# Schematic.net
KiCad netlist of a schematic drawn in Altium Designer
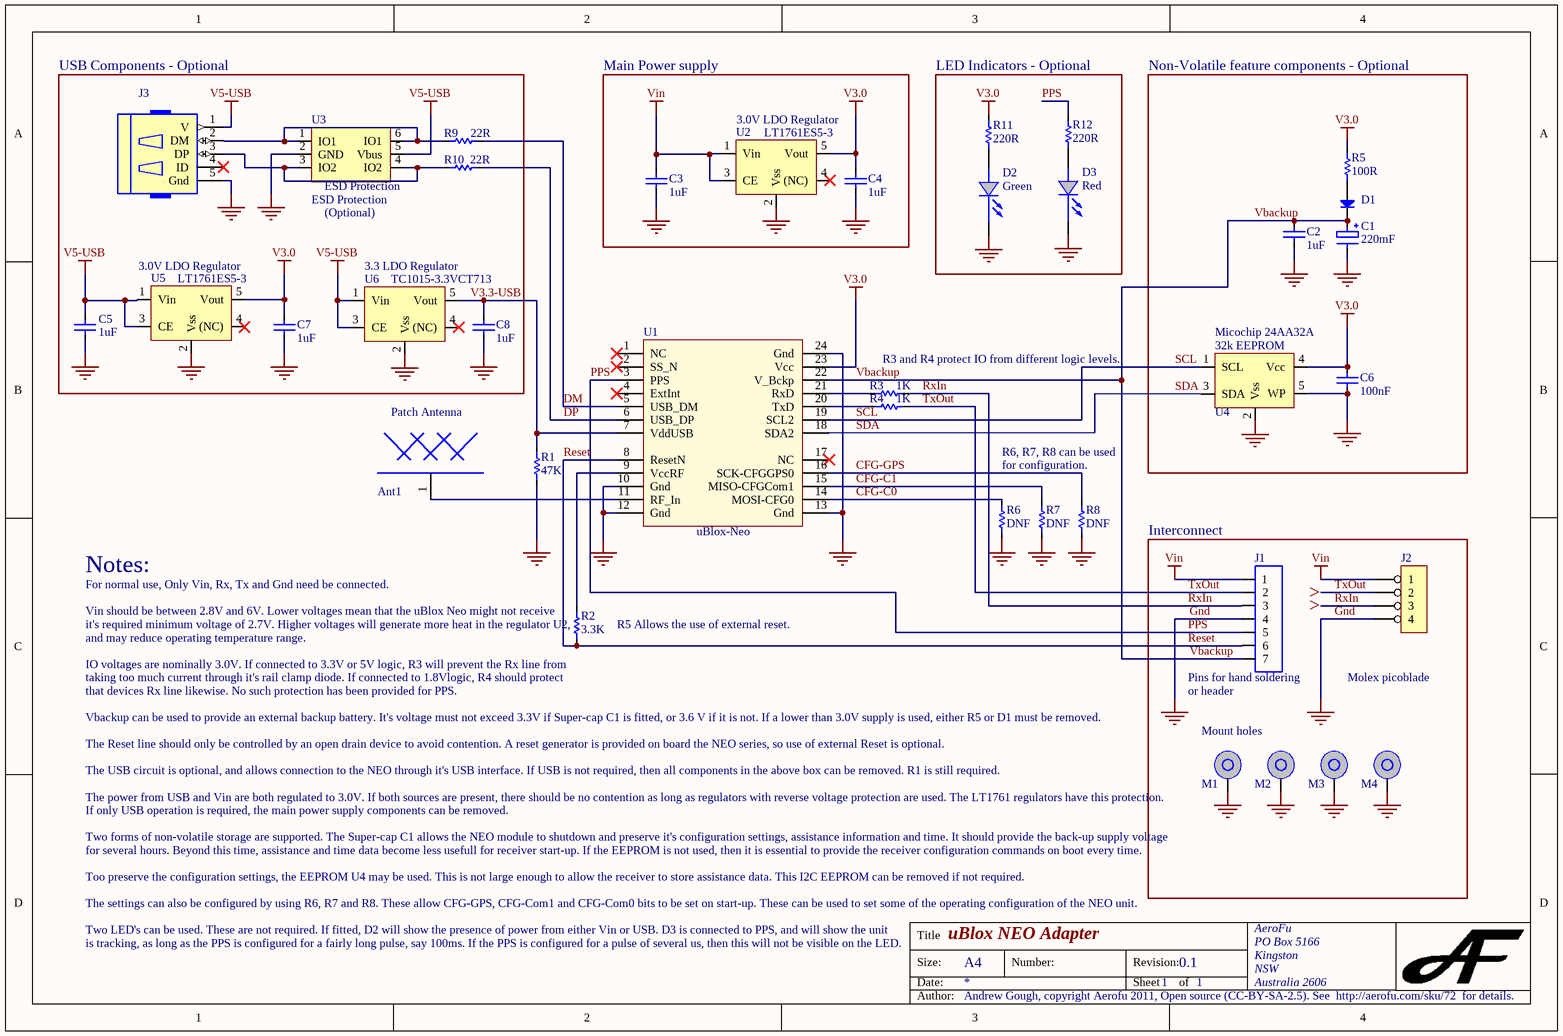
[diagram p0: Schematic.SchDoc]

(export (version "E")
  (design (tool "Eeschema 10.0.6"))
  (components
    (comp (ref "Ant1")
      (value "Patch Antenna")
      (footprint "Patch-25mm")
      (libsource (lib "Schlib1") (part "Patch Antenna"))
    )
    (comp (ref "C1")
      (value "220mF")
      (footprint "Supercap-6.8mm")
      (description "SuperCap")
      (fields (field (name "Comment") "Capacitor_SuperCap"))
      (libsource (lib "Schlib1") (part "Capacitor_SuperCap"))
    )
    (comp (ref "C2")
      (value "1uF")
      (footprint "0603")
      (description "Capacitor (Semiconductor SIM Model)")
      (fields (field (name "Comment") "Capacitor"))
      (libsource (lib "Schlib1") (part "Capacitor"))
    )
    (comp (ref "C3")
      (value "1uF")
      (footprint "0603")
      (description "Capacitor (Semiconductor SIM Model)")
      (fields (field (name "Comment") "Capacitor"))
      (libsource (lib "Schlib1") (part "Capacitor"))
    )
    (comp (ref "C4")
      (value "1uF")
      (footprint "0603")
      (description "Capacitor (Semiconductor SIM Model)")
      (fields (field (name "Comment") "Capacitor"))
      (libsource (lib "Schlib1") (part "Capacitor"))
    )
    (comp (ref "C5")
      (value "1uF")
      (footprint "0603")
      (description "Capacitor (Semiconductor SIM Model)")
      (fields (field (name "Comment") "Capacitor"))
      (libsource (lib "Schlib1") (part "Capacitor"))
    )
    (comp (ref "C6")
      (value "100nF")
      (footprint "0603")
      (description "Capacitor (Semiconductor SIM Model)")
      (fields (field (name "Comment") "Capacitor"))
      (libsource (lib "Schlib1") (part "Capacitor"))
    )
    (comp (ref "C7")
      (value "1uF")
      (footprint "0603")
      (description "Capacitor (Semiconductor SIM Model)")
      (fields (field (name "Comment") "Capacitor"))
      (libsource (lib "Schlib1") (part "Capacitor"))
    )
    (comp (ref "C8")
      (value "1uF")
      (footprint "0603")
      (description "Capacitor (Semiconductor SIM Model)")
      (fields (field (name "Comment") "Capacitor"))
      (libsource (lib "Schlib1") (part "Capacitor"))
    )
    (comp (ref "D1")
      (value "Diode BAS116")
      (footprint "SOT23-3")
      (description "Silicon Low Leakage Diode")
      (fields (field (name "PUBLISHER") "Altium Limited"))
      (libsource (lib "Schlib1") (part "Diode BAS116"))
    )
    (comp (ref "D2") (value "Green") (footprint "0603 - LED") (libsource (lib "Schlib1.1") (part "LED")))
    (comp (ref "D3") (value "Red") (footprint "0603 - LED") (libsource (lib "Schlib1.1") (part "LED")))
    (comp (ref "J1")
      (value "SPI Header")
      (footprint "HDR7X1-2.54")
      (libsource (lib "Schlib1.1") (part "7 Way header 7x1"))
    )
    (comp (ref "J2")
      (value "Socket 4x1")
      (footprint "Molex Picoblade 4 Pin socket")
      (description "Socket")
      (libsource (lib "Schlib1") (part "4 Way Socket 4x1"))
    )
    (comp (ref "J3")
      (value "USB-MiniB")
      (footprint "Mini-USB")
      (description "USB Connector")
      (libsource (lib "Schlib1") (part "USB-MiniB"))
    )
    (comp (ref "M1")
      (value "Screw Hole")
      (footprint "MOUNT HOLE")
      (description "Mount Hole")
      (libsource (lib "Schlib1.1") (part "Screw Hole"))
    )
    (comp (ref "M2")
      (value "Screw Hole")
      (footprint "MOUNT HOLE")
      (description "Mount Hole")
      (libsource (lib "Schlib1.1") (part "Screw Hole"))
    )
    (comp (ref "M3")
      (value "Screw Hole")
      (footprint "MOUNT HOLE")
      (description "Mount Hole")
      (libsource (lib "Schlib1.1") (part "Screw Hole"))
    )
    (comp (ref "M4")
      (value "Screw Hole")
      (footprint "MOUNT HOLE")
      (description "Mount Hole")
      (libsource (lib "Schlib1.1") (part "Screw Hole"))
    )
    (comp (ref "R1")
      (value "47K")
      (footprint "0603")
      (description "Resistor")
      (libsource (lib "Schlib1") (part "Resistor"))
    )
    (comp (ref "R2")
      (value "3.3K")
      (footprint "0603")
      (description "Resistor")
      (libsource (lib "Schlib1.1") (part "Resistor"))
    )
    (comp (ref "R3")
      (value "1K")
      (footprint "0603")
      (description "Resistor")
      (libsource (lib "Schlib1.1") (part "Resistor"))
    )
    (comp (ref "R4")
      (value "1K")
      (footprint "0603")
      (description "Resistor")
      (libsource (lib "Schlib1.1") (part "Resistor"))
    )
    (comp (ref "R5")
      (value "100R")
      (footprint "0603")
      (description "Resistor")
      (libsource (lib "Schlib1") (part "Resistor"))
    )
    (comp (ref "R6")
      (value "DNF")
      (footprint "0603")
      (description "Resistor")
      (libsource (lib "Schlib1.1") (part "Resistor"))
    )
    (comp (ref "R7")
      (value "DNF")
      (footprint "0603")
      (description "Resistor")
      (libsource (lib "Schlib1.1") (part "Resistor"))
    )
    (comp (ref "R8")
      (value "DNF")
      (footprint "0603")
      (description "Resistor")
      (libsource (lib "Schlib1.1") (part "Resistor"))
    )
    (comp (ref "R9")
      (value "22R")
      (footprint "0603")
      (description "Resistor")
      (libsource (lib "Schlib1") (part "Resistor"))
    )
    (comp (ref "R10")
      (value "22R")
      (footprint "0603")
      (description "Resistor")
      (libsource (lib "Schlib1") (part "Resistor"))
    )
    (comp (ref "R11")
      (value "220R")
      (footprint "0603")
      (description "Resistor")
      (libsource (lib "Schlib1.1") (part "Resistor"))
    )
    (comp (ref "R12")
      (value "220R")
      (footprint "0603")
      (description "Resistor")
      (libsource (lib "Schlib1.1") (part "Resistor"))
    )
    (comp (ref "U1")
      (value "uBlox-Neo")
      (footprint "uBlox-NEO")
      (libsource (lib "Schlib1") (part "uBlox-Neo"))
    )
    (comp (ref "U2")
      (value "LT1761ES5-3")
      (footprint "Sot23-5")
      (libsource (lib "Schlib1") (part "Regulator-5Pin"))
    )
    (comp (ref "U3")
      (value "ESD Protection")
      (footprint "Sot23-6")
      (description "USBLC6-2")
      (libsource (lib "Schlib1.1") (part "USBLC6-2"))
    )
    (comp (ref "U4")
      (value "32k EEPROM")
      (footprint "Sot23-5")
      (description "24AA32A")
      (libsource (lib "Schlib1.1") (part "24AA32A"))
    )
    (comp (ref "U5")
      (value "LT1761ES5-3")
      (footprint "Sot23-5")
      (libsource (lib "Schlib1") (part "Regulator-5Pin"))
    )
    (comp (ref "U6")
      (value "TC1015-3.3VCT713")
      (footprint "Sot23-5")
      (libsource (lib "Schlib1") (part "Regulator-5Pin"))
    )
  )
  (nets
    (net (code "1") (name "/CFG-C0") (class "Default")
      (node (ref "R6") (pin "2") (pinfunction "2_2") (pintype "passive"))
      (node (ref "U1") (pin "14") (pinfunction "MOSI-CFG0_14") (pintype "passive"))
    )
    (net (code "2") (name "/CFG-C1") (class "Default")
      (node (ref "R7") (pin "2") (pinfunction "2_2") (pintype "passive"))
      (node (ref "U1") (pin "15") (pinfunction "MISO-CFGCom1_15") (pintype "passive"))
    )
    (net (code "3") (name "/CFG-GPS") (class "Default")
      (node (ref "R8") (pin "2") (pinfunction "2_2") (pintype "passive"))
      (node (ref "U1") (pin "16") (pinfunction "SCK-CFGGPS0_16") (pintype "passive"))
    )
    (net (code "4") (name "/DM") (class "Default")
      (node (ref "R9") (pin "1") (pinfunction "1_1") (pintype "passive"))
      (node (ref "U1") (pin "5") (pinfunction "USB_DM_5") (pintype "passive"))
    )
    (net (code "5") (name "/DP") (class "Default")
      (node (ref "R10") (pin "1") (pinfunction "1_1") (pintype "passive"))
      (node (ref "U1") (pin "6") (pinfunction "USB_DP_6") (pintype "passive"))
    )
    (net (code "6") (name "/PPS") (class "Default")
      (node (ref "J1") (pin "5") (pinfunction "5_5") (pintype "passive"))
      (node (ref "R12") (pin "2") (pinfunction "2_2") (pintype "passive"))
      (node (ref "U1") (pin "3") (pinfunction "PPS_3") (pintype "passive"))
    )
    (net (code "7") (name "/Reset") (class "Default")
      (node (ref "J1") (pin "6") (pinfunction "6_6") (pintype "passive"))
      (node (ref "R2") (pin "1") (pinfunction "1_1") (pintype "passive"))
      (node (ref "U1") (pin "8") (pinfunction "ResetN_8") (pintype "passive"))
    )
    (net (code "8") (name "/RxIn") (class "Default")
      (node (ref "J1") (pin "3") (pinfunction "3_3") (pintype "passive"))
      (node (ref "J2") (pin "3") (pinfunction "3_3") (pintype "passive"))
      (node (ref "R3") (pin "1") (pinfunction "1_1") (pintype "passive"))
    )
    (net (code "9") (name "/SCL") (class "Default")
      (node (ref "U1") (pin "19") (pinfunction "SCL2_19") (pintype "passive"))
      (node (ref "U4") (pin "1") (pinfunction "SCL_1") (pintype "passive"))
    )
    (net (code "11") (name "/SDA") (class "Default")
      (node (ref "U1") (pin "18") (pinfunction "SDA2_18") (pintype "passive"))
      (node (ref "U4") (pin "3") (pinfunction "SDA_3") (pintype "passive"))
    )
    (net (code "12") (name "/TxOut") (class "Default")
      (node (ref "J1") (pin "2") (pinfunction "2_2") (pintype "passive"))
      (node (ref "J2") (pin "2") (pinfunction "2_2") (pintype "passive"))
      (node (ref "R4") (pin "1") (pinfunction "1_1") (pintype "passive"))
    )
    (net (code "13") (name "/V3.3-USB") (class "Default")
      (node (ref "C8") (pin "2") (pinfunction "2_2") (pintype "passive"))
      (node (ref "R1") (pin "2") (pinfunction "2_2") (pintype "passive"))
      (node (ref "U1") (pin "7") (pinfunction "VddUSB_7") (pintype "passive"))
      (node (ref "U6") (pin "5") (pinfunction "Vout_5") (pintype "passive"))
    )
    (net (code "14") (name "/Vbackup") (class "Default")
      (node (ref "C1") (pin "2") (pinfunction "2_2") (pintype "passive"))
      (node (ref "C2") (pin "2") (pinfunction "2_2") (pintype "passive"))
      (node (ref "D1") (pin "3") (pinfunction "K_3") (pintype "passive"))
      (node (ref "J1") (pin "7") (pinfunction "7_7") (pintype "passive"))
      (node (ref "U1") (pin "22") (pinfunction "V_Bckp_22") (pintype "passive"))
    )
    (net (code "15") (name "GND") (class "Default")
      (node (ref "C1") (pin "1") (pinfunction "1_1") (pintype "passive"))
      (node (ref "C2") (pin "1") (pinfunction "1_1") (pintype "passive"))
      (node (ref "C3") (pin "1") (pinfunction "1_1") (pintype "passive"))
      (node (ref "C4") (pin "1") (pinfunction "1_1") (pintype "passive"))
      (node (ref "C5") (pin "1") (pinfunction "1_1") (pintype "passive"))
      (node (ref "C6") (pin "1") (pinfunction "1_1") (pintype "passive"))
      (node (ref "C7") (pin "1") (pinfunction "1_1") (pintype "passive"))
      (node (ref "C8") (pin "1") (pinfunction "1_1") (pintype "passive"))
      (node (ref "D2") (pin "2") (pinfunction "CATHODE_2") (pintype "passive"))
      (node (ref "D3") (pin "2") (pinfunction "CATHODE_2") (pintype "passive"))
      (node (ref "J1") (pin "4") (pinfunction "4_4") (pintype "passive"))
      (node (ref "J2") (pin "4") (pinfunction "4_4") (pintype "passive"))
      (node (ref "J3") (pin "5") (pinfunction "Gnd_5") (pintype "power_in"))
      (node (ref "M1") (pin "1") (pinfunction "1_1") (pintype "passive"))
      (node (ref "M2") (pin "1") (pinfunction "1_1") (pintype "passive"))
      (node (ref "M3") (pin "1") (pinfunction "1_1") (pintype "passive"))
      (node (ref "M4") (pin "1") (pinfunction "1_1") (pintype "passive"))
      (node (ref "R1") (pin "1") (pinfunction "1_1") (pintype "passive"))
      (node (ref "R6") (pin "1") (pinfunction "1_1") (pintype "passive"))
      (node (ref "R7") (pin "1") (pinfunction "1_1") (pintype "passive"))
      (node (ref "R8") (pin "1") (pinfunction "1_1") (pintype "passive"))
      (node (ref "U1") (pin "10") (pinfunction "Gnd_10") (pintype "passive"))
      (node (ref "U1") (pin "12") (pinfunction "Gnd_12") (pintype "passive"))
      (node (ref "U1") (pin "13") (pinfunction "Gnd_13") (pintype "passive"))
      (node (ref "U1") (pin "24") (pinfunction "Gnd_24") (pintype "passive"))
      (node (ref "U2") (pin "2") (pinfunction "Vss_2") (pintype "passive"))
      (node (ref "U3") (pin "2") (pinfunction "GND_2") (pintype "passive"))
      (node (ref "U4") (pin "2") (pinfunction "Vss_2") (pintype "passive"))
      (node (ref "U4") (pin "5") (pinfunction "WP_5") (pintype "passive"))
      (node (ref "U5") (pin "2") (pinfunction "Vss_2") (pintype "passive"))
      (node (ref "U6") (pin "2") (pinfunction "Vss_2") (pintype "passive"))
    )
    (net (code "16") (name "Net-(D1-A)") (class "Default")
      (node (ref "D1") (pin "1") (pinfunction "A_1") (pintype "passive"))
      (node (ref "R5") (pin "1") (pinfunction "1_1") (pintype "passive"))
    )
    (net (code "17") (name "Net-(D2-ANODE)") (class "Default")
      (node (ref "D2") (pin "1") (pinfunction "ANODE_1") (pintype "passive"))
      (node (ref "R11") (pin "1") (pinfunction "1_1") (pintype "passive"))
    )
    (net (code "18") (name "Net-(D3-ANODE)") (class "Default")
      (node (ref "D3") (pin "1") (pinfunction "ANODE_1") (pintype "passive"))
      (node (ref "R12") (pin "1") (pinfunction "1_1") (pintype "passive"))
    )
    (net (code "19") (name "Net-(J3-DM)") (class "Default")
      (node (ref "J3") (pin "2") (pinfunction "DM_2") (pintype "bidirectional"))
      (node (ref "R9") (pin "2") (pinfunction "2_2") (pintype "passive"))
      (node (ref "U3") (pin "1") (pinfunction "IO1_1") (pintype "passive"))
      (node (ref "U3") (pin "6") (pinfunction "IO1_6") (pintype "passive"))
    )
    (net (code "20") (name "Net-(J3-DP)") (class "Default")
      (node (ref "J3") (pin "3") (pinfunction "DP_3") (pintype "bidirectional"))
      (node (ref "R10") (pin "2") (pinfunction "2_2") (pintype "passive"))
      (node (ref "U3") (pin "3") (pinfunction "IO2_3") (pintype "passive"))
      (node (ref "U3") (pin "4") (pinfunction "IO2_4") (pintype "passive"))
    )
    (net (code "21") (name "Net-(U1-RF_In)") (class "Default")
      (node (ref "Ant1") (pin "1") (pinfunction "1_1") (pintype "passive"))
      (node (ref "U1") (pin "11") (pinfunction "RF_In_11") (pintype "passive"))
    )
    (net (code "22") (name "Net-(U1-RxD)") (class "Default")
      (node (ref "R3") (pin "2") (pinfunction "2_2") (pintype "passive"))
      (node (ref "U1") (pin "21") (pinfunction "RxD_21") (pintype "passive"))
    )
    (net (code "23") (name "Net-(U1-TxD)") (class "Default")
      (node (ref "R4") (pin "2") (pinfunction "2_2") (pintype "passive"))
      (node (ref "U1") (pin "20") (pinfunction "TxD_20") (pintype "passive"))
    )
    (net (code "24") (name "Net-(U1-VccRF)") (class "Default")
      (node (ref "R2") (pin "2") (pinfunction "2_2") (pintype "passive"))
      (node (ref "U1") (pin "9") (pinfunction "VccRF_9") (pintype "passive"))
    )
    (net (code "25") (name "V3.0") (class "Default")
      (node (ref "C4") (pin "2") (pinfunction "2_2") (pintype "passive"))
      (node (ref "C6") (pin "2") (pinfunction "2_2") (pintype "passive"))
      (node (ref "C7") (pin "2") (pinfunction "2_2") (pintype "passive"))
      (node (ref "R11") (pin "2") (pinfunction "2_2") (pintype "passive"))
      (node (ref "R5") (pin "2") (pinfunction "2_2") (pintype "passive"))
      (node (ref "U1") (pin "23") (pinfunction "Vcc_23") (pintype "passive"))
      (node (ref "U2") (pin "5") (pinfunction "Vout_5") (pintype "passive"))
      (node (ref "U4") (pin "4") (pinfunction "Vcc_4") (pintype "passive"))
      (node (ref "U5") (pin "5") (pinfunction "Vout_5") (pintype "passive"))
    )
    (net (code "26") (name "V5-USB") (class "Default")
      (node (ref "C5") (pin "2") (pinfunction "2_2") (pintype "passive"))
      (node (ref "J3") (pin "1") (pinfunction "V_1") (pintype "output"))
      (node (ref "U3") (pin "5") (pinfunction "Vbus_5") (pintype "passive"))
      (node (ref "U5") (pin "1") (pinfunction "Vin_1") (pintype "passive"))
      (node (ref "U5") (pin "3") (pinfunction "CE_3") (pintype "passive"))
      (node (ref "U6") (pin "1") (pinfunction "Vin_1") (pintype "passive"))
      (node (ref "U6") (pin "3") (pinfunction "CE_3") (pintype "passive"))
    )
    (net (code "27") (name "Vin") (class "Default")
      (node (ref "C3") (pin "2") (pinfunction "2_2") (pintype "passive"))
      (node (ref "J1") (pin "1") (pinfunction "1_1") (pintype "passive"))
      (node (ref "J2") (pin "1") (pinfunction "1_1") (pintype "passive"))
      (node (ref "U2") (pin "1") (pinfunction "Vin_1") (pintype "passive"))
      (node (ref "U2") (pin "3") (pinfunction "CE_3") (pintype "passive"))
    )
    (net (code "28") (name "unconnected-(J3-ID-Pad4)") (class "Default")
      (node (ref "J3") (pin "4") (pinfunction "ID_4") (pintype "power_in+no_connect"))
    )
    (net (code "29") (name "unconnected-(J3-MT-Pad5)") (class "Default")
      (node (ref "J3") (pin "5") (pinfunction "MT_5") (pintype "passive"))
    )
    (net (code "30") (name "unconnected-(J3-MT-Pad6)") (class "Default")
      (node (ref "J3") (pin "6") (pinfunction "MT_6") (pintype "passive"))
    )
    (net (code "31") (name "unconnected-(U1-ExtInt-Pad4)") (class "Default")
      (node (ref "U1") (pin "4") (pinfunction "ExtInt_4") (pintype "passive+no_connect"))
    )
    (net (code "32") (name "unconnected-(U1-NC-Pad1)") (class "Default")
      (node (ref "U1") (pin "1") (pinfunction "NC_1") (pintype "passive+no_connect"))
    )
    (net (code "33") (name "unconnected-(U1-NC-Pad17)") (class "Default")
      (node (ref "U1") (pin "17") (pinfunction "NC_17") (pintype "passive+no_connect"))
    )
    (net (code "34") (name "unconnected-(U1-SS_N-Pad2)") (class "Default")
      (node (ref "U1") (pin "2") (pinfunction "SS_N_2") (pintype "passive+no_connect"))
    )
    (net (code "35") (name "unconnected-(U2-(NC)-Pad4)") (class "Default")
      (node (ref "U2") (pin "4") (pinfunction "(NC)_4") (pintype "passive+no_connect"))
    )
    (net (code "36") (name "unconnected-(U5-(NC)-Pad4)") (class "Default")
      (node (ref "U5") (pin "4") (pinfunction "(NC)_4") (pintype "passive"))
    )
    (net (code "37") (name "unconnected-(U6-(NC)-Pad4)") (class "Default")
      (node (ref "U6") (pin "4") (pinfunction "(NC)_4") (pintype "passive+no_connect"))
    )
  )
)
